# cc2530-LR-standalone-router.net
KiCad netlist of a schematic drawn in EAGLE
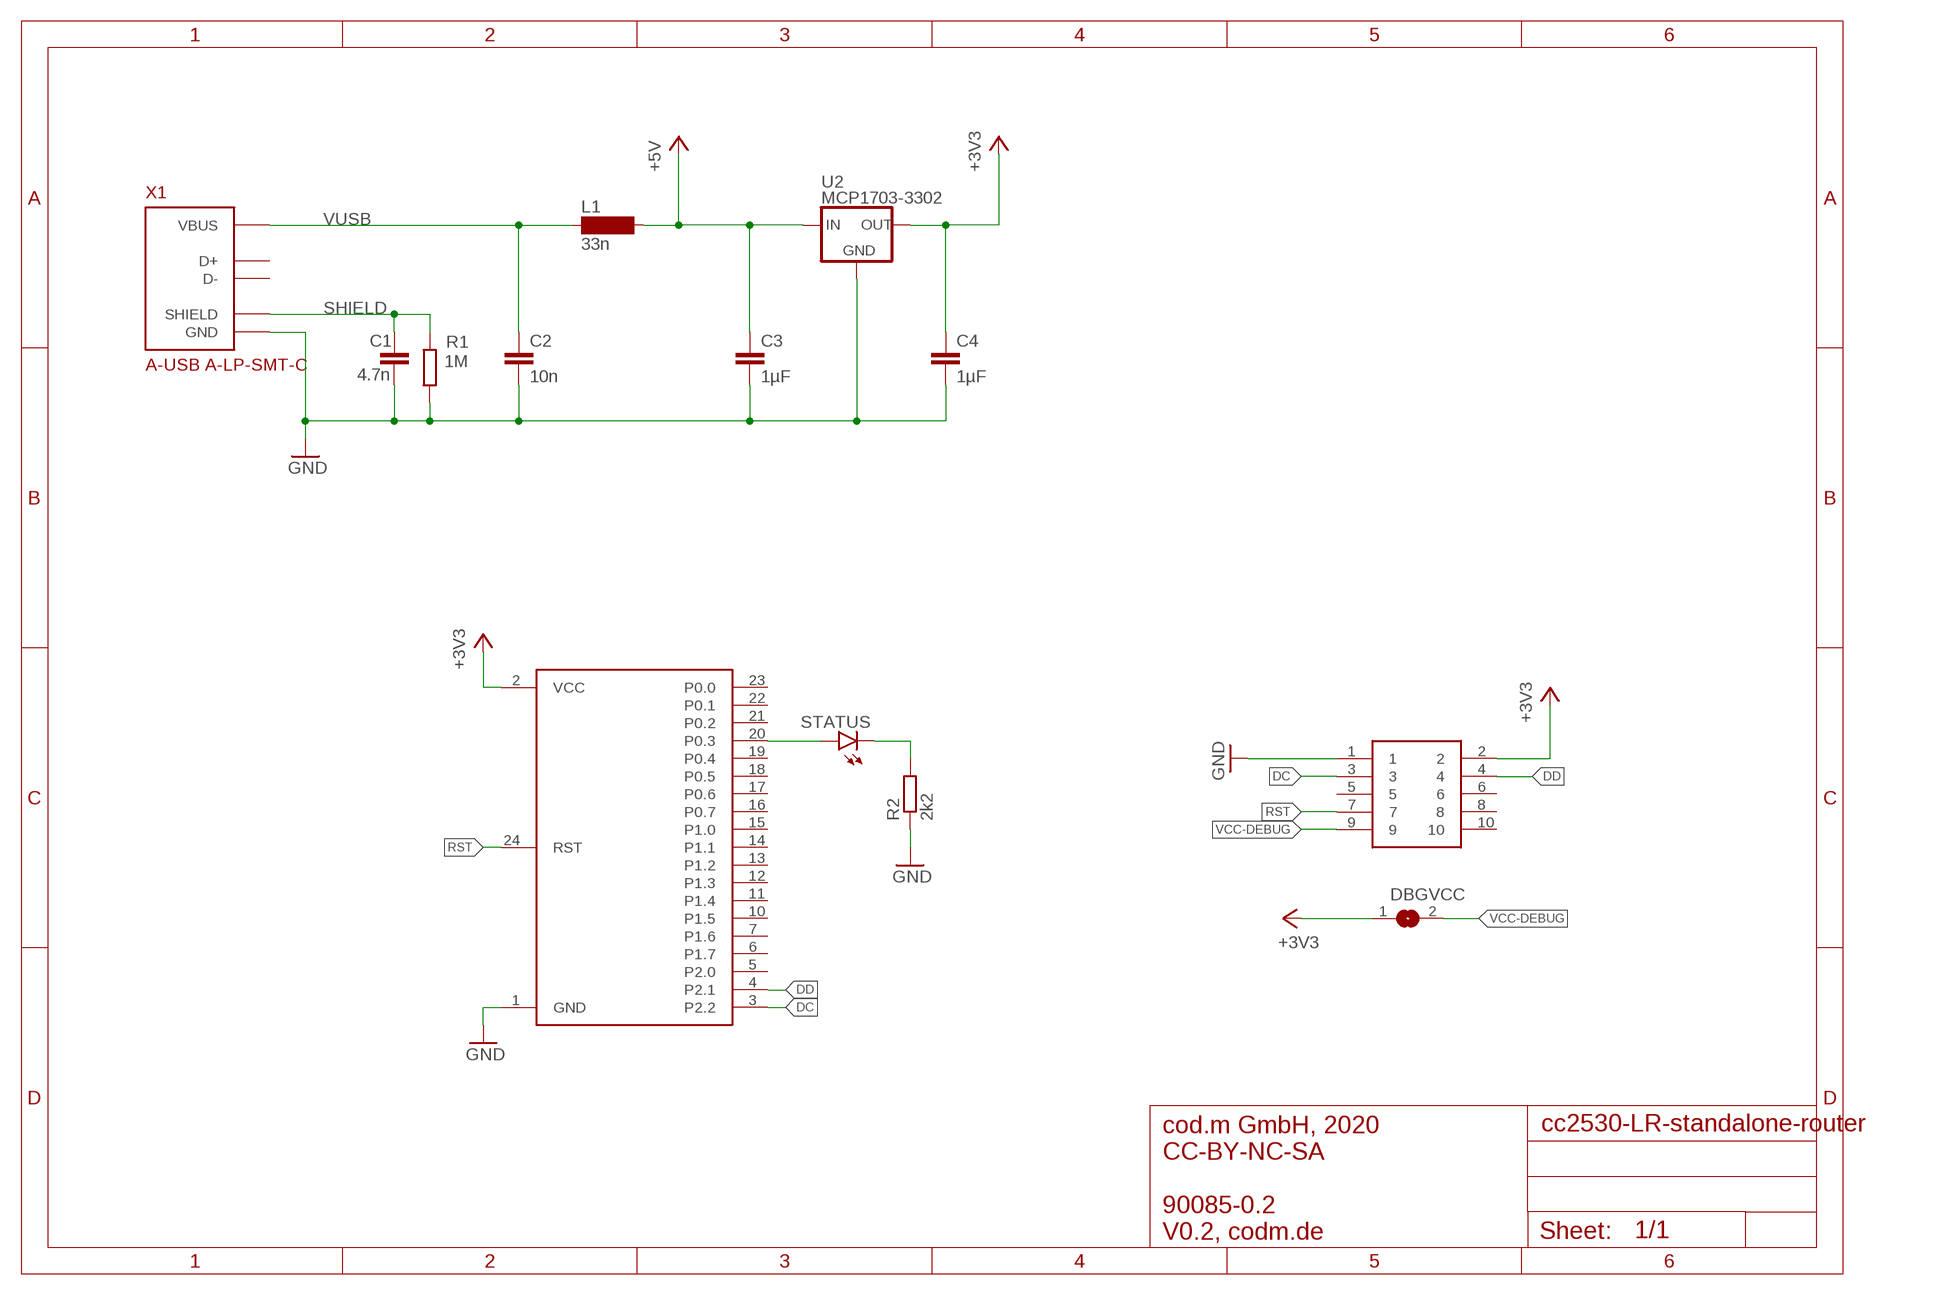
[diagram p0: schematic, sheet 1]

(export (version "E")
  (design (tool "Eeschema 10.0.6"))
  (components
    (comp (ref "C1")
      (value "4.7n")
      (footprint "eagle-import:C1206")
      (libsource (lib "eagle-import") (part "C-EUC1206"))
    )
    (comp (ref "C2")
      (value "10n")
      (footprint "eagle-import:C1206")
      (libsource (lib "eagle-import") (part "C-EUC1206"))
    )
    (comp (ref "C3")
      (value "1µF")
      (footprint "eagle-import:C1206")
      (libsource (lib "eagle-import") (part "resistor_348_C-EUC1206"))
    )
    (comp (ref "C4")
      (value "1µF")
      (footprint "eagle-import:C1206")
      (libsource (lib "eagle-import") (part "resistor_348_C-EUC1206"))
    )
    (comp (ref "DBGVCC")
      (value "SJ")
      (footprint "eagle-import:SJ")
      (libsource (lib "eagle-import") (part "SJ"))
    )
    (comp (ref "DEBUG")
      (value "20021121-00010C4LF")
      (footprint "eagle-import:2002112100010C4LF")
      (fields (field (name "MOUSER_PART_NUMBER") "649-202112100010C4LF"))
      (libsource (lib "eagle-import") (part "20021121-00010C4LF"))
    )
    (comp (ref "L1")
      (value "33n")
      (footprint "eagle-import:SM-1206")
      (libsource (lib "eagle-import") (part "SM-1206"))
    )
    (comp (ref "R1")
      (value "1M")
      (footprint "eagle-import:R1206")
      (libsource (lib "eagle-import") (part "R-EU_R1206"))
    )
    (comp (ref "R2")
      (value "2k2")
      (footprint "eagle-import:R1206")
      (libsource (lib "eagle-import") (part "R-EU_R1206"))
    )
    (comp (ref "STATUS")
      (value "LEDCHIPLED_1206")
      (footprint "eagle-import:CHIPLED_1206")
      (libsource (lib "eagle-import") (part "LEDCHIPLED_1206"))
    )
    (comp (ref "U$5")
      (value "E18-MS1PA2-PCB")
      (footprint "eagle-import:E18-MS1PA2-PCB")
      (libsource (lib "eagle-import") (part "E18-MS1PA2-PCB"))
    )
    (comp (ref "U2")
      (value "MCP1703-3302")
      (footprint "eagle-import:SOT-22-3")
      (libsource (lib "eagle-import") (part "V_REG_SOT-22-3"))
    )
    (comp (ref "X1")
      (value "A-USB A-LP-SMT-C")
      (footprint "eagle-import:A-USB_A-LP-SMT-C")
      (libsource (lib "eagle-import") (part "USB-1.0/1.1/2.0-STANDARD-A/B_A-LP-SMT-C"))
    )
  )
  (nets
    (net (code "1") (name "+3V3") (class "Default")
      (node (ref "C4") (pin "1") (pinfunction "1_1") (pintype "passive"))
      (node (ref "DBGVCC") (pin "1") (pinfunction "1_1") (pintype "passive"))
      (node (ref "DEBUG") (pin "2") (pinfunction "2_2") (pintype "bidirectional"))
      (node (ref "U$5") (pin "2") (pinfunction "VCC_2") (pintype "bidirectional"))
      (node (ref "U2") (pin "3") (pinfunction "OUT_3") (pintype "passive"))
    )
    (net (code "2") (name "+5V") (class "Default")
      (node (ref "C3") (pin "1") (pinfunction "1_1") (pintype "passive"))
      (node (ref "L1") (pin "2") (pinfunction "2_2") (pintype "passive"))
      (node (ref "U2") (pin "1") (pinfunction "IN_1") (pintype "input"))
    )
    (net (code "3") (name "/SHIELD") (class "Default")
      (node (ref "C1") (pin "1") (pinfunction "1_1") (pintype "passive"))
      (node (ref "R1") (pin "1") (pinfunction "1_1") (pintype "passive"))
      (node (ref "X1") (pin "S1") (pinfunction "SHIELD_S1") (pintype "bidirectional"))
      (node (ref "X1") (pin "S2") (pinfunction "SHIELD_S2") (pintype "bidirectional"))
    )
    (net (code "4") (name "/VUSB") (class "Default")
      (node (ref "C2") (pin "1") (pinfunction "1_1") (pintype "passive"))
      (node (ref "L1") (pin "1") (pinfunction "1_1") (pintype "passive"))
      (node (ref "X1") (pin "1") (pinfunction "VBUS_1") (pintype "bidirectional"))
    )
    (net (code "5") (name "DC") (class "Default")
      (node (ref "DEBUG") (pin "3") (pinfunction "3_3") (pintype "bidirectional"))
      (node (ref "U$5") (pin "3") (pinfunction "P2.2_3") (pintype "bidirectional"))
    )
    (net (code "6") (name "DD") (class "Default")
      (node (ref "DEBUG") (pin "4") (pinfunction "4_4") (pintype "bidirectional"))
      (node (ref "U$5") (pin "4") (pinfunction "P2.1_4") (pintype "bidirectional"))
    )
    (net (code "7") (name "GND") (class "Default")
      (node (ref "C1") (pin "2") (pinfunction "2_2") (pintype "passive"))
      (node (ref "C2") (pin "2") (pinfunction "2_2") (pintype "passive"))
      (node (ref "C3") (pin "2") (pinfunction "2_2") (pintype "passive"))
      (node (ref "C4") (pin "2") (pinfunction "2_2") (pintype "passive"))
      (node (ref "DEBUG") (pin "1") (pinfunction "1_1") (pintype "bidirectional"))
      (node (ref "R1") (pin "2") (pinfunction "2_2") (pintype "passive"))
      (node (ref "R2") (pin "1") (pinfunction "1_1") (pintype "passive"))
      (node (ref "U$5") (pin "1") (pinfunction "GND_1") (pintype "bidirectional"))
      (node (ref "U2") (pin "2") (pinfunction "GND_2") (pintype "input"))
      (node (ref "U2") (pin "4") (pinfunction "GND_4") (pintype "input"))
      (node (ref "X1") (pin "4") (pinfunction "GND_4") (pintype "bidirectional"))
    )
    (net (code "8") (name "Net-(R2-Pad2)") (class "Default")
      (node (ref "R2") (pin "2") (pinfunction "2_2") (pintype "passive"))
      (node (ref "STATUS") (pin "C") (pinfunction "C_C") (pintype "passive"))
    )
    (net (code "9") (name "Net-(U$5-P0.3)") (class "Default")
      (node (ref "STATUS") (pin "A") (pinfunction "A_A") (pintype "passive"))
      (node (ref "U$5") (pin "20") (pinfunction "P0.3_20") (pintype "bidirectional"))
    )
    (net (code "10") (name "RST") (class "Default")
      (node (ref "DEBUG") (pin "7") (pinfunction "7_7") (pintype "bidirectional"))
      (node (ref "U$5") (pin "24") (pinfunction "RST_24") (pintype "bidirectional"))
    )
    (net (code "11") (name "VCC-DEBUG") (class "Default")
      (node (ref "DBGVCC") (pin "2") (pinfunction "2_2") (pintype "passive"))
      (node (ref "DEBUG") (pin "9") (pinfunction "9_9") (pintype "bidirectional"))
    )
    (net (code "12") (name "unconnected-(DEBUG-Pad5)") (class "Default")
      (node (ref "DEBUG") (pin "5") (pinfunction "5_5") (pintype "bidirectional"))
    )
    (net (code "13") (name "unconnected-(DEBUG-Pad6)") (class "Default")
      (node (ref "DEBUG") (pin "6") (pinfunction "6_6") (pintype "bidirectional"))
    )
    (net (code "14") (name "unconnected-(DEBUG-Pad8)") (class "Default")
      (node (ref "DEBUG") (pin "8") (pinfunction "8_8") (pintype "bidirectional"))
    )
    (net (code "15") (name "unconnected-(DEBUG-Pad10)") (class "Default")
      (node (ref "DEBUG") (pin "10") (pinfunction "10_10") (pintype "bidirectional"))
    )
    (net (code "16") (name "unconnected-(U$5-P0.0-Pad23)") (class "Default")
      (node (ref "U$5") (pin "23") (pinfunction "P0.0_23") (pintype "bidirectional"))
    )
    (net (code "17") (name "unconnected-(U$5-P0.1-Pad22)") (class "Default")
      (node (ref "U$5") (pin "22") (pinfunction "P0.1_22") (pintype "bidirectional"))
    )
    (net (code "18") (name "unconnected-(U$5-P0.2-Pad21)") (class "Default")
      (node (ref "U$5") (pin "21") (pinfunction "P0.2_21") (pintype "bidirectional"))
    )
    (net (code "19") (name "unconnected-(U$5-P0.4-Pad19)") (class "Default")
      (node (ref "U$5") (pin "19") (pinfunction "P0.4_19") (pintype "bidirectional"))
    )
    (net (code "20") (name "unconnected-(U$5-P0.5-Pad18)") (class "Default")
      (node (ref "U$5") (pin "18") (pinfunction "P0.5_18") (pintype "bidirectional"))
    )
    (net (code "21") (name "unconnected-(U$5-P0.6-Pad17)") (class "Default")
      (node (ref "U$5") (pin "17") (pinfunction "P0.6_17") (pintype "bidirectional"))
    )
    (net (code "22") (name "unconnected-(U$5-P0.7-Pad16)") (class "Default")
      (node (ref "U$5") (pin "16") (pinfunction "P0.7_16") (pintype "bidirectional"))
    )
    (net (code "23") (name "unconnected-(U$5-P1.0-Pad15)") (class "Default")
      (node (ref "U$5") (pin "15") (pinfunction "P1.0_15") (pintype "bidirectional"))
    )
    (net (code "24") (name "unconnected-(U$5-P1.1-Pad14)") (class "Default")
      (node (ref "U$5") (pin "14") (pinfunction "P1.1_14") (pintype "bidirectional"))
    )
    (net (code "25") (name "unconnected-(U$5-P1.2-Pad13)") (class "Default")
      (node (ref "U$5") (pin "13") (pinfunction "P1.2_13") (pintype "bidirectional"))
    )
    (net (code "26") (name "unconnected-(U$5-P1.3-Pad12)") (class "Default")
      (node (ref "U$5") (pin "12") (pinfunction "P1.3_12") (pintype "bidirectional"))
    )
    (net (code "27") (name "unconnected-(U$5-P1.4-Pad11)") (class "Default")
      (node (ref "U$5") (pin "11") (pinfunction "P1.4_11") (pintype "bidirectional"))
    )
    (net (code "28") (name "unconnected-(U$5-P1.5-Pad10)") (class "Default")
      (node (ref "U$5") (pin "10") (pinfunction "P1.5_10") (pintype "bidirectional"))
    )
    (net (code "29") (name "unconnected-(U$5-P1.6-Pad7)") (class "Default")
      (node (ref "U$5") (pin "7") (pinfunction "P1.6_7") (pintype "bidirectional"))
    )
    (net (code "30") (name "unconnected-(U$5-P1.7-Pad6)") (class "Default")
      (node (ref "U$5") (pin "6") (pinfunction "P1.7_6") (pintype "bidirectional"))
    )
    (net (code "31") (name "unconnected-(U$5-P2.0-Pad5)") (class "Default")
      (node (ref "U$5") (pin "5") (pinfunction "P2.0_5") (pintype "bidirectional"))
    )
    (net (code "32") (name "unconnected-(X1-D+-Pad3)") (class "Default")
      (node (ref "X1") (pin "3") (pinfunction "D+_3") (pintype "bidirectional"))
    )
    (net (code "33") (name "unconnected-(X1-D--Pad2)") (class "Default")
      (node (ref "X1") (pin "2") (pinfunction "D-_2") (pintype "bidirectional"))
    )
  )
)
